# PM12_Supply_LED.net
KiCad netlist of a schematic drawn in Altium Designer
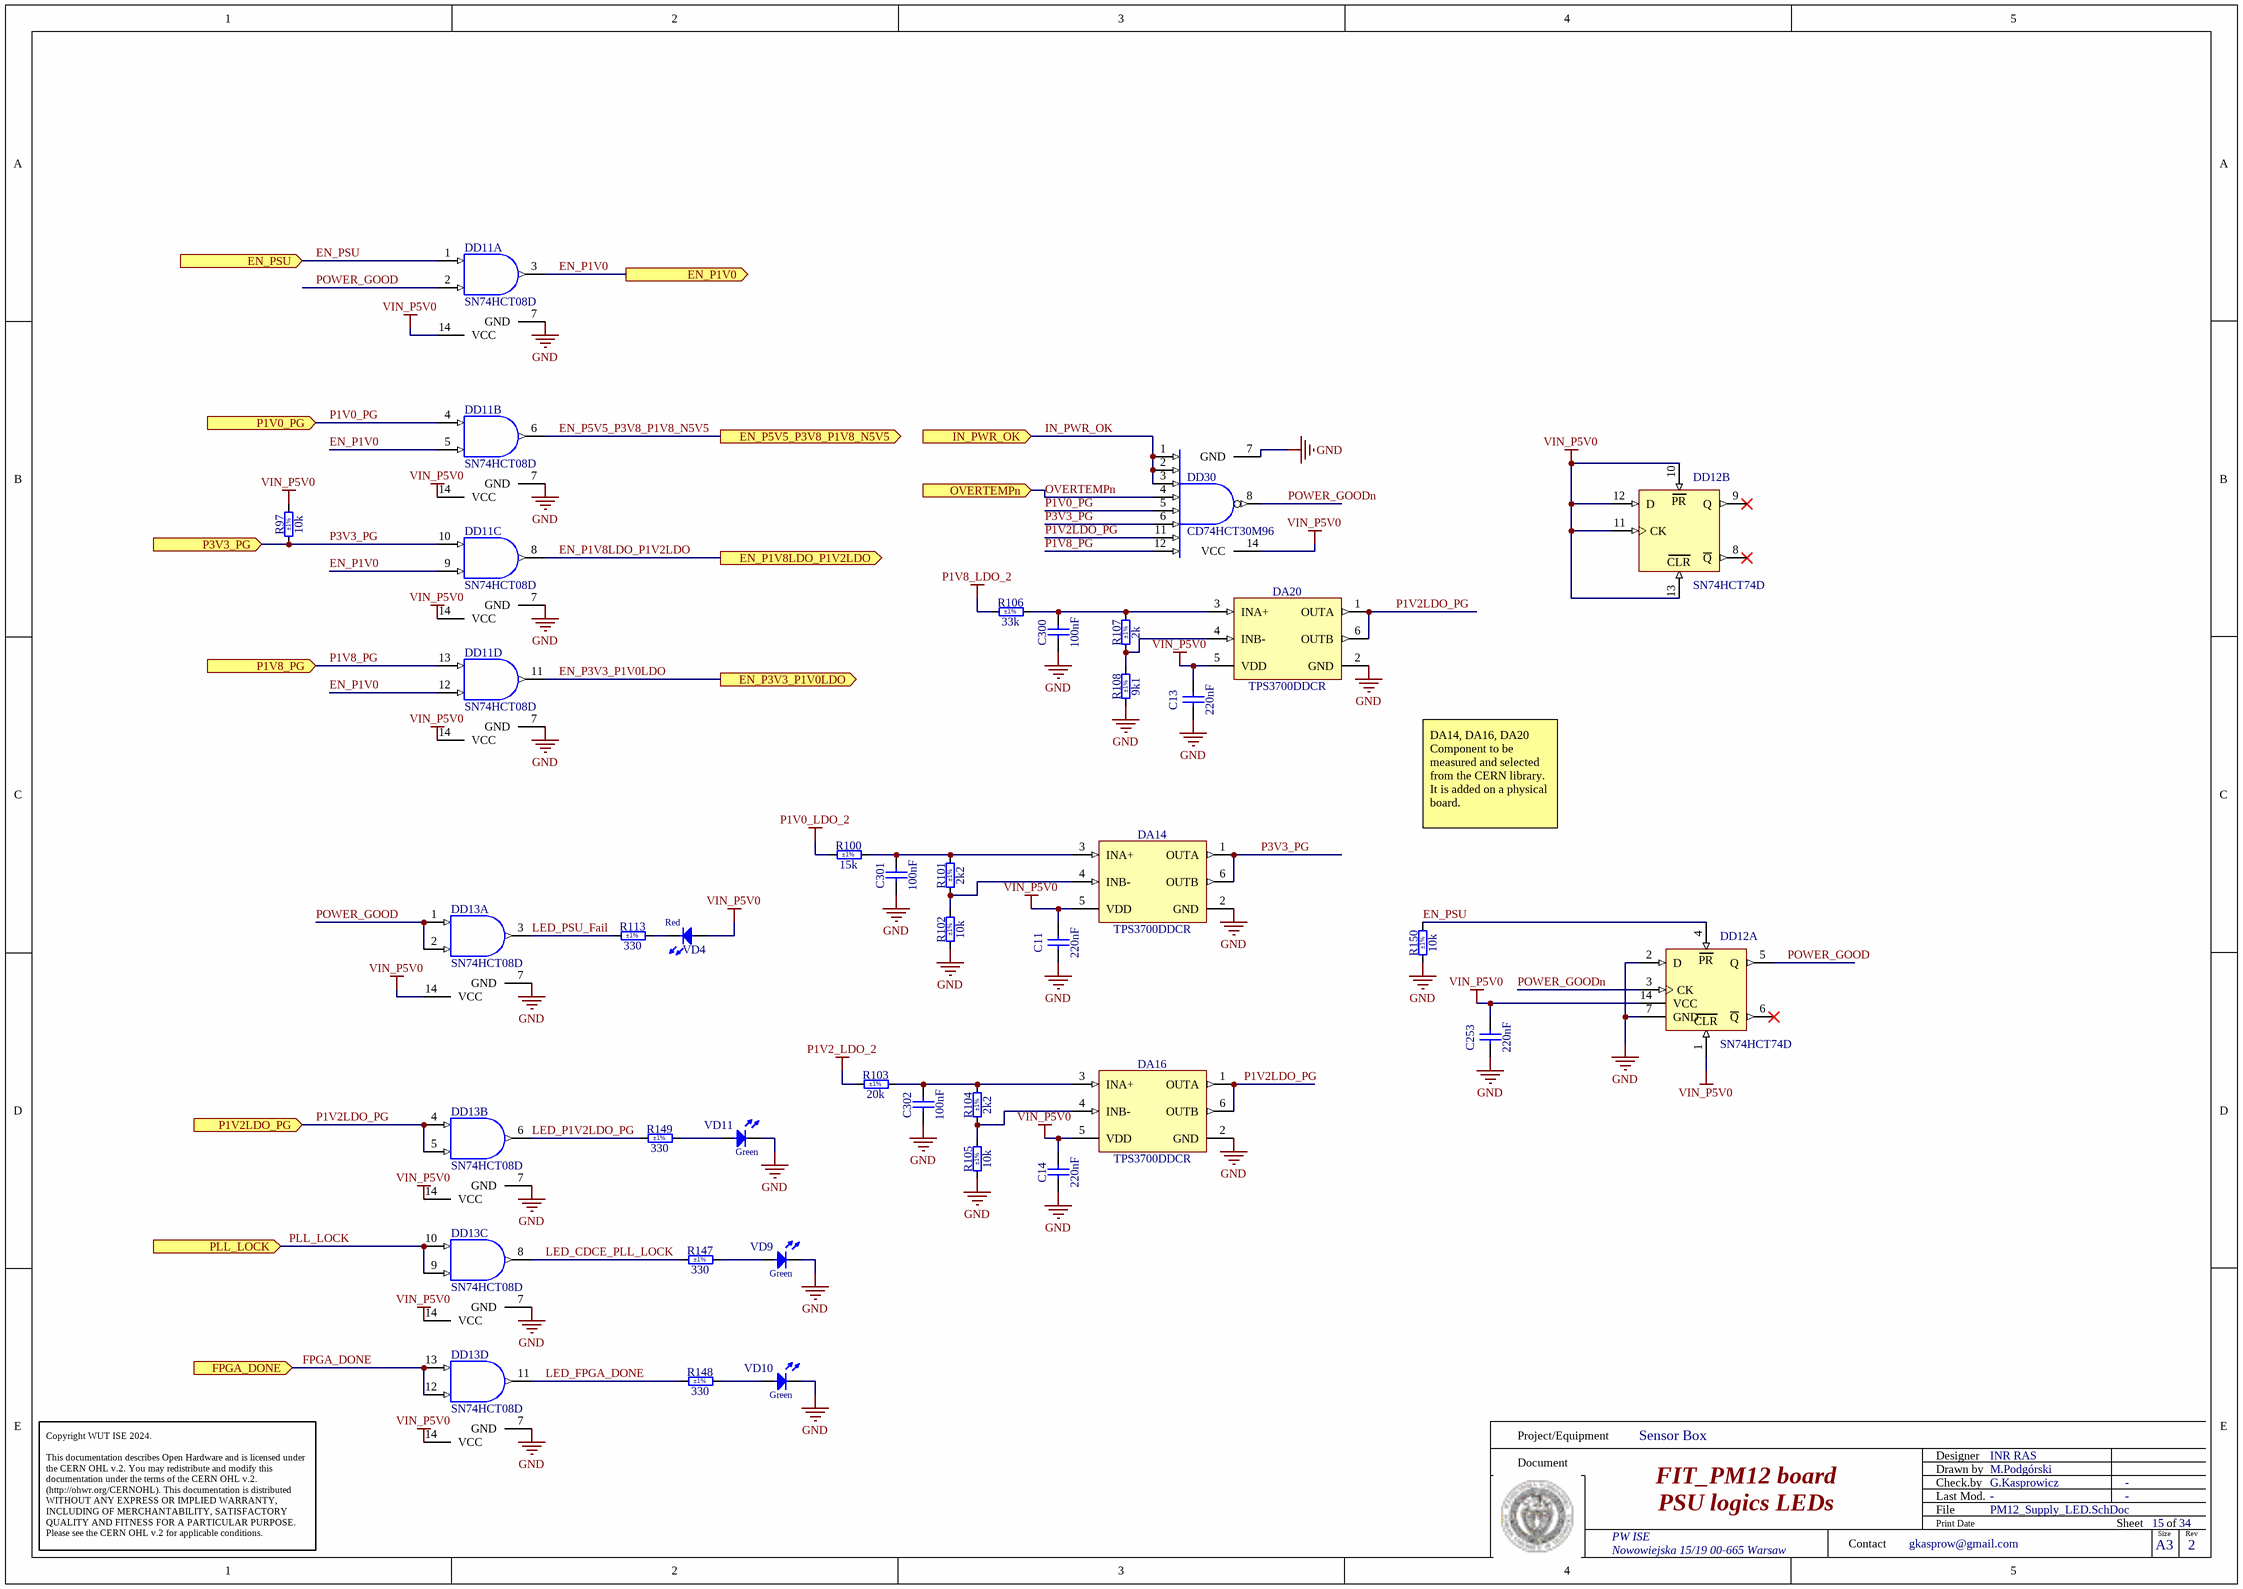
[diagram p0: PM12_Supply_LED.SchDoc]

(export (version "E")
  (design (tool "Eeschema 10.0.6"))
  (components
    (comp (ref "C11")
      (value "220nF")
      (footprint "CAPC2012X135N")
      (description "Non-polarised capacitor")
      (fields
        (field (name "PART NUMBER") "CC0805_220NF_50V_10%_X7R")
        (field (name "VOLTAGE") "50V")
        (field (name "AUTHOR") "CERN DEM JLC")
      )
      (libsource (lib "Capacitors") (part "Capacitor - non polarized"))
    )
    (comp (ref "C13")
      (value "220nF")
      (footprint "CAPC2012X135N")
      (description "Non-polarised capacitor")
      (fields
        (field (name "PART NUMBER") "CC0805_220NF_50V_10%_X7R")
        (field (name "VOLTAGE") "50V")
        (field (name "AUTHOR") "CERN DEM JLC")
      )
      (libsource (lib "Capacitors") (part "Capacitor - non polarized"))
    )
    (comp (ref "C14")
      (value "220nF")
      (footprint "CAPC2012X135N")
      (description "Non-polarised capacitor")
      (fields
        (field (name "PART NUMBER") "CC0805_220NF_50V_10%_X7R")
        (field (name "VOLTAGE") "50V")
        (field (name "AUTHOR") "CERN DEM JLC")
      )
      (libsource (lib "Capacitors") (part "Capacitor - non polarized"))
    )
    (comp (ref "C253")
      (value "220nF")
      (footprint "CAPC2012X135N")
      (description "Non-polarised capacitor")
      (fields
        (field (name "PART NUMBER") "CC0805_220NF_50V_10%_X7R")
        (field (name "VOLTAGE") "50V")
        (field (name "AUTHOR") "CERN DEM JLC")
      )
      (libsource (lib "Capacitors") (part "Capacitor - non polarized"))
    )
    (comp (ref "C300")
      (value "100nF")
      (footprint "CAPC1005X55N")
      (description "Non-polarised capacitor")
      (fields
        (field (name "PART NUMBER") "CC0402_100NF_50V_10%_X7R")
        (field (name "VOLTAGE") "50V")
        (field (name "AUTHOR") "CERN DEM MR")
      )
      (libsource (lib "Capacitors") (part "Capacitor - non polarized"))
    )
    (comp (ref "C301")
      (value "100nF")
      (footprint "CAPC1005X55N")
      (description "Non-polarised capacitor")
      (fields
        (field (name "PART NUMBER") "CC0402_100NF_50V_10%_X7R")
        (field (name "VOLTAGE") "50V")
        (field (name "AUTHOR") "CERN DEM MR")
      )
      (libsource (lib "Capacitors") (part "Capacitor - non polarized"))
    )
    (comp (ref "C302")
      (value "100nF")
      (footprint "CAPC1005X55N")
      (description "Non-polarised capacitor")
      (fields
        (field (name "PART NUMBER") "CC0402_100NF_50V_10%_X7R")
        (field (name "VOLTAGE") "50V")
        (field (name "AUTHOR") "CERN DEM MR")
      )
      (libsource (lib "Capacitors") (part "Capacitor - non polarized"))
    )
    (comp (ref "DA14")
      (value "TPS3700DDCR")
      (footprint "SOT95P280X110-6N")
      (description "Window Comparator for Over- and Undervoltage Detection")
      (fields (field (name "MANUFACTURER") "TEXAS INSTRUMENTS") (field (name "AUTHOR") "CERN DEM JMW"))
      (libsource (lib "ICs And Semiconductors") (part "TPS3700DDC"))
    )
    (comp (ref "DA16")
      (value "TPS3700DDCR")
      (footprint "SOT95P280X110-6N")
      (description "Window Comparator for Over- and Undervoltage Detection")
      (fields (field (name "MANUFACTURER") "TEXAS INSTRUMENTS") (field (name "AUTHOR") "CERN DEM JMW"))
      (libsource (lib "ICs And Semiconductors") (part "TPS3700DDC"))
    )
    (comp (ref "DA20")
      (value "TPS3700DDCR")
      (footprint "SOT95P280X110-6N")
      (description "Window Comparator for Over- and Undervoltage Detection")
      (fields (field (name "MANUFACTURER") "TEXAS INSTRUMENTS") (field (name "AUTHOR") "CERN DEM JMW"))
      (libsource (lib "ICs And Semiconductors") (part "TPS3700DDC"))
    )
    (comp (ref "DD11")
      (value "SN74HCT08D")
      (footprint "SOIC127P600X175-14N")
      (description "Quad 2-Input AND Gate")
      (fields (field (name "MANUFACTURER") "TEXAS INSTRUMENTS") (field (name "AUTHOR") "CERN DEM HF"))
      (libsource (lib "ICs And Semiconductors") (part "7408"))
    )
    (comp (ref "DD12")
      (value "SN74HCT74D")
      (footprint "SOIC127P600X175-14N")
      (description "Dual D-Type Flip Flop with Preset and Clear")
      (fields (field (name "MANUFACTURER") "TEXAS INSTRUMENTS") (field (name "AUTHOR") "CERN DEM JLC"))
      (libsource (lib "ICs And Semiconductors") (part "7474"))
    )
    (comp (ref "DD13")
      (value "SN74HCT08D")
      (footprint "SOIC127P600X175-14N")
      (description "Quad 2-Input AND Gate")
      (fields (field (name "MANUFACTURER") "TEXAS INSTRUMENTS") (field (name "AUTHOR") "CERN DEM HF"))
      (libsource (lib "ICs And Semiconductors") (part "7408"))
    )
    (comp (ref "DD30")
      (value "CD74HCT30M96")
      (footprint "SOIC127P600X175-14N")
      (description "8-Input NAND Gate")
      (fields (field (name "MANUFACTURER") "TEXAS INSTRUMENTS") (field (name "AUTHOR") "CERN DEM HF"))
      (libsource (lib "ICs And Semiconductors") (part "7430"))
    )
    (comp (ref "R97")
      (value "10k")
      (footprint "RESC2012X60N")
      (description "Resistor - 1%")
      (fields
        (field (name "TOLERANCE") "±1%")
        (field (name "PART NUMBER") "R0805_10K_1%_0.125W_100PPM")
        (field (name "POWER") "0.125W")
        (field (name "AUTHOR") "CERN DEM JLC")
      )
      (libsource (lib "Resistors") (part "Resistor - 1%"))
    )
    (comp (ref "R100")
      (value "15k")
      (footprint "RESC2012X60N")
      (description "Resistor - 1%")
      (fields
        (field (name "TOLERANCE") "±1%")
        (field (name "PART NUMBER") "R0805_15K_1%_0.125W_100PPM")
        (field (name "POWER") "0.125W")
        (field (name "AUTHOR") "CERN DEM JLC")
      )
      (libsource (lib "Resistors") (part "Resistor - 1%"))
    )
    (comp (ref "R101")
      (value "2k2")
      (footprint "RESC2012X60N")
      (description "Resistor - 1%")
      (fields
        (field (name "TOLERANCE") "±1%")
        (field (name "PART NUMBER") "R0805_2K2_1%_0.125W_100PPM")
        (field (name "POWER") "0.125W")
        (field (name "AUTHOR") "CERN DEM JLC")
      )
      (libsource (lib "Resistors") (part "Resistor - 1%"))
    )
    (comp (ref "R102")
      (value "10k")
      (footprint "RESC2012X60N")
      (description "Resistor - 1%")
      (fields
        (field (name "TOLERANCE") "±1%")
        (field (name "PART NUMBER") "R0805_10K_1%_0.125W_100PPM")
        (field (name "POWER") "0.125W")
        (field (name "AUTHOR") "CERN DEM JLC")
      )
      (libsource (lib "Resistors") (part "Resistor - 1%"))
    )
    (comp (ref "R103")
      (value "20k")
      (footprint "RESC2012X60N")
      (description "Resistor - 1%")
      (fields
        (field (name "TOLERANCE") "±1%")
        (field (name "PART NUMBER") "R0805_20K_1%_0.125W_100PPM")
        (field (name "POWER") "0.125W")
        (field (name "AUTHOR") "CERN DEM JLC")
      )
      (libsource (lib "Resistors") (part "Resistor - 1%"))
    )
    (comp (ref "R104")
      (value "2k2")
      (footprint "RESC2012X60N")
      (description "Resistor - 1%")
      (fields
        (field (name "TOLERANCE") "±1%")
        (field (name "PART NUMBER") "R0805_2K2_1%_0.125W_100PPM")
        (field (name "POWER") "0.125W")
        (field (name "AUTHOR") "CERN DEM JLC")
      )
      (libsource (lib "Resistors") (part "Resistor - 1%"))
    )
    (comp (ref "R105")
      (value "10k")
      (footprint "RESC2012X60N")
      (description "Resistor - 1%")
      (fields
        (field (name "TOLERANCE") "±1%")
        (field (name "PART NUMBER") "R0805_10K_1%_0.125W_100PPM")
        (field (name "POWER") "0.125W")
        (field (name "AUTHOR") "CERN DEM JLC")
      )
      (libsource (lib "Resistors") (part "Resistor - 1%"))
    )
    (comp (ref "R106")
      (value "33k")
      (footprint "RESC2012X60N")
      (description "Resistor - 1%")
      (fields
        (field (name "TOLERANCE") "±1%")
        (field (name "PART NUMBER") "R0805_33K_1%_0.125W_100PPM")
        (field (name "POWER") "0.125W")
        (field (name "AUTHOR") "CERN DEM JLC")
      )
      (libsource (lib "Resistors") (part "Resistor - 1%"))
    )
    (comp (ref "R107")
      (value "2k")
      (footprint "RESC2012X60N")
      (description "Resistor - 1%")
      (fields
        (field (name "TOLERANCE") "±1%")
        (field (name "PART NUMBER") "R0805_2K_1%_0.125W_100PPM")
        (field (name "POWER") "0.125W")
        (field (name "AUTHOR") "CERN DEM JLC")
      )
      (libsource (lib "Resistors") (part "Resistor - 1%"))
    )
    (comp (ref "R108")
      (value "9k1")
      (footprint "RESC2012X60N")
      (description "Resistor - 1%")
      (fields
        (field (name "TOLERANCE") "±1%")
        (field (name "PART NUMBER") "R0805_9K1_1%_0.125W_100PPM")
        (field (name "POWER") "0.125W")
        (field (name "AUTHOR") "CERN DEM JLC")
      )
      (libsource (lib "Resistors") (part "Resistor - 1%"))
    )
    (comp (ref "R113")
      (value "330")
      (footprint "RESC2012X60N")
      (description "Resistor - 1%")
      (fields
        (field (name "TOLERANCE") "±1%")
        (field (name "PART NUMBER") "R0805_330R_1%_0.125W_100PPM")
        (field (name "POWER") "0.125W")
        (field (name "AUTHOR") "CERN DEM JLC")
      )
      (libsource (lib "Resistors") (part "Resistor - 1%"))
    )
    (comp (ref "R147")
      (value "330")
      (footprint "RESC2012X60N")
      (description "Resistor - 1%")
      (fields
        (field (name "TOLERANCE") "±1%")
        (field (name "PART NUMBER") "R0805_330R_1%_0.125W_100PPM")
        (field (name "POWER") "0.125W")
        (field (name "AUTHOR") "CERN DEM JLC")
      )
      (libsource (lib "Resistors") (part "Resistor - 1%"))
    )
    (comp (ref "R148")
      (value "330")
      (footprint "RESC2012X60N")
      (description "Resistor - 1%")
      (fields
        (field (name "TOLERANCE") "±1%")
        (field (name "PART NUMBER") "R0805_330R_1%_0.125W_100PPM")
        (field (name "POWER") "0.125W")
        (field (name "AUTHOR") "CERN DEM JLC")
      )
      (libsource (lib "Resistors") (part "Resistor - 1%"))
    )
    (comp (ref "R149")
      (value "330")
      (footprint "RESC2012X60N")
      (description "Resistor - 1%")
      (fields
        (field (name "TOLERANCE") "±1%")
        (field (name "PART NUMBER") "R0805_330R_1%_0.125W_100PPM")
        (field (name "POWER") "0.125W")
        (field (name "AUTHOR") "CERN DEM JLC")
      )
      (libsource (lib "Resistors") (part "Resistor - 1%"))
    )
    (comp (ref "R150")
      (value "10k")
      (footprint "RESC2012X60N")
      (description "Resistor - 1%")
      (fields
        (field (name "TOLERANCE") "±1%")
        (field (name "PART NUMBER") "R0805_10K_1%_0.125W_100PPM")
        (field (name "POWER") "0.125W")
        (field (name "AUTHOR") "CERN DEM JLC")
      )
      (libsource (lib "Resistors") (part "Resistor - 1%"))
    )
    (comp (ref "VD4")
      (value "Red")
      (footprint "LED_KINGBRIGHT_KPT-2012SURCK")
      (description "LED Red 1C 2A")
      (fields
        (field (name "PART NUMBER") "LED_KINGBRIGHT_KPT-2012SURCK")
        (field (name "MANUFACTURER") "KINGBRIGHT")
        (field (name "AUTHOR") "CERN DEM BC")
      )
      (libsource (lib "ICs And Semiconductors") (part "LED Red 1C 2A"))
    )
    (comp (ref "VD9")
      (value "Green")
      (footprint "LED_KINGBRIGHT_KP-2012LSGC")
      (description "LED Green 1C 2A")
      (fields
        (field (name "PART NUMBER") "LED_KINGBRIGHT_KP-2012LSGC")
        (field (name "MANUFACTURER") "KINGBRIGHT")
        (field (name "AUTHOR") "CERN DEM BC")
      )
      (libsource (lib "ICs And Semiconductors") (part "LED Green 1C 2A"))
    )
    (comp (ref "VD10")
      (value "Green")
      (footprint "LED_KINGBRIGHT_KP-2012LSGC")
      (description "LED Green 1C 2A")
      (fields
        (field (name "PART NUMBER") "LED_KINGBRIGHT_KP-2012LSGC")
        (field (name "MANUFACTURER") "KINGBRIGHT")
        (field (name "AUTHOR") "CERN DEM BC")
      )
      (libsource (lib "ICs And Semiconductors") (part "LED Green 1C 2A"))
    )
    (comp (ref "VD11")
      (value "Green")
      (footprint "LED_KINGBRIGHT_KP-2012LSGC")
      (description "LED Green 1C 2A")
      (fields
        (field (name "PART NUMBER") "LED_KINGBRIGHT_KP-2012LSGC")
        (field (name "MANUFACTURER") "KINGBRIGHT")
        (field (name "AUTHOR") "CERN DEM BC")
      )
      (libsource (lib "ICs And Semiconductors") (part "LED Green 1C 2A"))
    )
  )
  (nets
    (net (code "1") (name "/EN_P1V0") (class "Default")
      (node (ref "DD11") (pin "12") (pinfunction "B_12") (pintype "input"))
      (node (ref "DD11") (pin "3") (pinfunction "Y_3") (pintype "output"))
      (node (ref "DD11") (pin "5") (pinfunction "B_5") (pintype "input"))
      (node (ref "DD11") (pin "9") (pinfunction "B_9") (pintype "input"))
    )
    (net (code "2") (name "/EN_P1V8LDO_P1V2LDO") (class "Default")
      (node (ref "DD11") (pin "8") (pinfunction "Y_8") (pintype "output"))
    )
    (net (code "3") (name "/EN_P3V3_P1V0LDO") (class "Default")
      (node (ref "DD11") (pin "11") (pinfunction "Y_11") (pintype "output"))
    )
    (net (code "4") (name "/EN_P5V5_P3V8_P1V8_N5V5") (class "Default")
      (node (ref "DD11") (pin "6") (pinfunction "Y_6") (pintype "output"))
    )
    (net (code "5") (name "/EN_PSU") (class "Default")
      (node (ref "DD11") (pin "1") (pinfunction "A_1") (pintype "input"))
      (node (ref "DD12") (pin "4") (pinfunction "~{PR}_4") (pintype "input"))
      (node (ref "R150") (pin "2") (pinfunction "2_2") (pintype "passive"))
    )
    (net (code "6") (name "/FPGA_DONE") (class "Default")
      (node (ref "DD13") (pin "12") (pinfunction "B_12") (pintype "input"))
      (node (ref "DD13") (pin "13") (pinfunction "A_13") (pintype "input"))
    )
    (net (code "7") (name "/IN_PWR_OK") (class "Default")
      (node (ref "DD30") (pin "1") (pinfunction "A_1") (pintype "input"))
      (node (ref "DD30") (pin "2") (pinfunction "B_2") (pintype "input"))
      (node (ref "DD30") (pin "3") (pinfunction "C_3") (pintype "input"))
    )
    (net (code "8") (name "/LED_CDCE_PLL_LOCK") (class "Default")
      (node (ref "DD13") (pin "8") (pinfunction "Y_8") (pintype "output"))
      (node (ref "R147") (pin "1") (pinfunction "1_1") (pintype "passive"))
    )
    (net (code "9") (name "/LED_FPGA_DONE") (class "Default")
      (node (ref "DD13") (pin "11") (pinfunction "Y_11") (pintype "output"))
      (node (ref "R148") (pin "1") (pinfunction "1_1") (pintype "passive"))
    )
    (net (code "10") (name "/LED_P1V2LDO_PG") (class "Default")
      (node (ref "DD13") (pin "6") (pinfunction "Y_6") (pintype "output"))
      (node (ref "R149") (pin "1") (pinfunction "1_1") (pintype "passive"))
    )
    (net (code "11") (name "/LED_PSU_Fail") (class "Default")
      (node (ref "DD13") (pin "3") (pinfunction "Y_3") (pintype "output"))
      (node (ref "R113") (pin "1") (pinfunction "1_1") (pintype "passive"))
    )
    (net (code "12") (name "/OVERTEMPn") (class "Default")
      (node (ref "DD30") (pin "4") (pinfunction "D_4") (pintype "input"))
    )
    (net (code "13") (name "/P1V0_PG") (class "Default")
      (node (ref "DD11") (pin "4") (pinfunction "A_4") (pintype "input"))
      (node (ref "DD30") (pin "5") (pinfunction "E_5") (pintype "input"))
    )
    (net (code "14") (name "/P1V2LDO_PG") (class "Default")
      (node (ref "DA16") (pin "1") (pinfunction "OUTA_1") (pintype "output"))
      (node (ref "DA16") (pin "6") (pinfunction "OUTB_6") (pintype "output"))
      (node (ref "DA20") (pin "1") (pinfunction "OUTA_1") (pintype "output"))
      (node (ref "DA20") (pin "6") (pinfunction "OUTB_6") (pintype "output"))
      (node (ref "DD13") (pin "4") (pinfunction "A_4") (pintype "input"))
      (node (ref "DD13") (pin "5") (pinfunction "B_5") (pintype "input"))
      (node (ref "DD30") (pin "11") (pinfunction "G_11") (pintype "input"))
    )
    (net (code "15") (name "/P1V8_PG") (class "Default")
      (node (ref "DD11") (pin "13") (pinfunction "A_13") (pintype "input"))
      (node (ref "DD30") (pin "12") (pinfunction "H_12") (pintype "input"))
    )
    (net (code "16") (name "/P3V3_PG") (class "Default")
      (node (ref "DA14") (pin "1") (pinfunction "OUTA_1") (pintype "output"))
      (node (ref "DA14") (pin "6") (pinfunction "OUTB_6") (pintype "output"))
      (node (ref "DD11") (pin "10") (pinfunction "A_10") (pintype "input"))
      (node (ref "DD30") (pin "6") (pinfunction "F_6") (pintype "input"))
      (node (ref "R97") (pin "1") (pinfunction "1_1") (pintype "passive"))
    )
    (net (code "17") (name "/PLL_LOCK") (class "Default")
      (node (ref "DD13") (pin "10") (pinfunction "A_10") (pintype "input"))
      (node (ref "DD13") (pin "9") (pinfunction "B_9") (pintype "input"))
    )
    (net (code "18") (name "/POWER_GOOD") (class "Default")
      (node (ref "DD11") (pin "2") (pinfunction "B_2") (pintype "input"))
      (node (ref "DD12") (pin "5") (pinfunction "Q_5") (pintype "output"))
      (node (ref "DD13") (pin "1") (pinfunction "A_1") (pintype "input"))
      (node (ref "DD13") (pin "2") (pinfunction "B_2") (pintype "input"))
    )
    (net (code "19") (name "/POWER_GOODn") (class "Default")
      (node (ref "DD12") (pin "3") (pinfunction "CK_3") (pintype "input"))
      (node (ref "DD30") (pin "8") (pinfunction "Y_8") (pintype "output"))
    )
    (net (code "20") (name "GND") (class "Default")
      (node (ref "C11") (pin "1") (pinfunction "1_1") (pintype "passive"))
      (node (ref "C13") (pin "1") (pinfunction "1_1") (pintype "passive"))
      (node (ref "C14") (pin "1") (pinfunction "1_1") (pintype "passive"))
      (node (ref "C253") (pin "1") (pinfunction "1_1") (pintype "passive"))
      (node (ref "C300") (pin "1") (pinfunction "1_1") (pintype "passive"))
      (node (ref "C301") (pin "1") (pinfunction "1_1") (pintype "passive"))
      (node (ref "C302") (pin "1") (pinfunction "1_1") (pintype "passive"))
      (node (ref "DA14") (pin "2") (pinfunction "GND_2") (pintype "power_in"))
      (node (ref "DA16") (pin "2") (pinfunction "GND_2") (pintype "power_in"))
      (node (ref "DA20") (pin "2") (pinfunction "GND_2") (pintype "power_in"))
      (node (ref "DD11") (pin "7") (pinfunction "GND_7") (pintype "power_in"))
      (node (ref "DD12") (pin "2") (pinfunction "D_2") (pintype "input"))
      (node (ref "DD12") (pin "7") (pinfunction "GND_7") (pintype "power_in"))
      (node (ref "DD13") (pin "7") (pinfunction "GND_7") (pintype "power_in"))
      (node (ref "DD30") (pin "7") (pinfunction "GND_7") (pintype "power_in"))
      (node (ref "R102") (pin "1") (pinfunction "1_1") (pintype "passive"))
      (node (ref "R105") (pin "1") (pinfunction "1_1") (pintype "passive"))
      (node (ref "R108") (pin "1") (pinfunction "1_1") (pintype "passive"))
      (node (ref "R150") (pin "1") (pinfunction "1_1") (pintype "passive"))
      (node (ref "VD10") (pin "1") (pinfunction "C_1") (pintype "passive"))
      (node (ref "VD11") (pin "1") (pinfunction "C_1") (pintype "passive"))
      (node (ref "VD9") (pin "1") (pinfunction "C_1") (pintype "passive"))
    )
    (net (code "21") (name "Net-(DA14-INA+)") (class "Default")
      (node (ref "C301") (pin "2") (pinfunction "2_2") (pintype "passive"))
      (node (ref "DA14") (pin "3") (pinfunction "INA+_3") (pintype "input"))
      (node (ref "R100") (pin "2") (pinfunction "2_2") (pintype "passive"))
      (node (ref "R101") (pin "2") (pinfunction "2_2") (pintype "passive"))
    )
    (net (code "22") (name "Net-(DA14-INB-)") (class "Default")
      (node (ref "DA14") (pin "4") (pinfunction "INB-_4") (pintype "input"))
      (node (ref "R101") (pin "1") (pinfunction "1_1") (pintype "passive"))
      (node (ref "R102") (pin "2") (pinfunction "2_2") (pintype "passive"))
    )
    (net (code "23") (name "Net-(DA16-INA+)") (class "Default")
      (node (ref "C302") (pin "2") (pinfunction "2_2") (pintype "passive"))
      (node (ref "DA16") (pin "3") (pinfunction "INA+_3") (pintype "input"))
      (node (ref "R103") (pin "2") (pinfunction "2_2") (pintype "passive"))
      (node (ref "R104") (pin "2") (pinfunction "2_2") (pintype "passive"))
    )
    (net (code "24") (name "Net-(DA16-INB-)") (class "Default")
      (node (ref "DA16") (pin "4") (pinfunction "INB-_4") (pintype "input"))
      (node (ref "R104") (pin "1") (pinfunction "1_1") (pintype "passive"))
      (node (ref "R105") (pin "2") (pinfunction "2_2") (pintype "passive"))
    )
    (net (code "25") (name "Net-(DA20-INA+)") (class "Default")
      (node (ref "C300") (pin "2") (pinfunction "2_2") (pintype "passive"))
      (node (ref "DA20") (pin "3") (pinfunction "INA+_3") (pintype "input"))
      (node (ref "R106") (pin "2") (pinfunction "2_2") (pintype "passive"))
      (node (ref "R107") (pin "2") (pinfunction "2_2") (pintype "passive"))
    )
    (net (code "26") (name "Net-(DA20-INB-)") (class "Default")
      (node (ref "DA20") (pin "4") (pinfunction "INB-_4") (pintype "input"))
      (node (ref "R107") (pin "1") (pinfunction "1_1") (pintype "passive"))
      (node (ref "R108") (pin "2") (pinfunction "2_2") (pintype "passive"))
    )
    (net (code "27") (name "Net-(VD4-C)") (class "Default")
      (node (ref "R113") (pin "2") (pinfunction "2_2") (pintype "passive"))
      (node (ref "VD4") (pin "1") (pinfunction "C_1") (pintype "passive"))
    )
    (net (code "28") (name "Net-(VD9-A)") (class "Default")
      (node (ref "R147") (pin "2") (pinfunction "2_2") (pintype "passive"))
      (node (ref "VD9") (pin "2") (pinfunction "A_2") (pintype "passive"))
    )
    (net (code "29") (name "Net-(VD10-A)") (class "Default")
      (node (ref "R148") (pin "2") (pinfunction "2_2") (pintype "passive"))
      (node (ref "VD10") (pin "2") (pinfunction "A_2") (pintype "passive"))
    )
    (net (code "30") (name "Net-(VD11-A)") (class "Default")
      (node (ref "R149") (pin "2") (pinfunction "2_2") (pintype "passive"))
      (node (ref "VD11") (pin "2") (pinfunction "A_2") (pintype "passive"))
    )
    (net (code "31") (name "P1V0_LDO_2") (class "Default")
      (node (ref "R100") (pin "1") (pinfunction "1_1") (pintype "passive"))
    )
    (net (code "32") (name "P1V2_LDO_2") (class "Default")
      (node (ref "R103") (pin "1") (pinfunction "1_1") (pintype "passive"))
    )
    (net (code "33") (name "P1V8_LDO_2") (class "Default")
      (node (ref "R106") (pin "1") (pinfunction "1_1") (pintype "passive"))
    )
    (net (code "34") (name "VIN_P5V0") (class "Default")
      (node (ref "C11") (pin "2") (pinfunction "2_2") (pintype "passive"))
      (node (ref "C13") (pin "2") (pinfunction "2_2") (pintype "passive"))
      (node (ref "C14") (pin "2") (pinfunction "2_2") (pintype "passive"))
      (node (ref "C253") (pin "2") (pinfunction "2_2") (pintype "passive"))
      (node (ref "DA14") (pin "5") (pinfunction "VDD_5") (pintype "power_in"))
      (node (ref "DA16") (pin "5") (pinfunction "VDD_5") (pintype "power_in"))
      (node (ref "DA20") (pin "5") (pinfunction "VDD_5") (pintype "power_in"))
      (node (ref "DD11") (pin "14") (pinfunction "VCC_14") (pintype "power_in"))
      (node (ref "DD12") (pin "1") (pinfunction "~{CLR}_1") (pintype "input"))
      (node (ref "DD12") (pin "10") (pinfunction "~{PR}_10") (pintype "input"))
      (node (ref "DD12") (pin "11") (pinfunction "CK_11") (pintype "input"))
      (node (ref "DD12") (pin "12") (pinfunction "D_12") (pintype "input"))
      (node (ref "DD12") (pin "13") (pinfunction "~{CLR}_13") (pintype "input"))
      (node (ref "DD12") (pin "14") (pinfunction "VCC_14") (pintype "power_in"))
      (node (ref "DD13") (pin "14") (pinfunction "VCC_14") (pintype "power_in"))
      (node (ref "DD30") (pin "14") (pinfunction "VCC_14") (pintype "power_in"))
      (node (ref "R97") (pin "2") (pinfunction "2_2") (pintype "passive"))
      (node (ref "VD4") (pin "2") (pinfunction "A_2") (pintype "passive"))
    )
    (net (code "35") (name "unconnected-(DD12A-~{Q}-Pad6)") (class "Default")
      (node (ref "DD12") (pin "6") (pinfunction "~{Q}_6") (pintype "output+no_connect"))
    )
    (net (code "36") (name "unconnected-(DD12B-Q-Pad9)") (class "Default")
      (node (ref "DD12") (pin "9") (pinfunction "Q_9") (pintype "output+no_connect"))
    )
    (net (code "37") (name "unconnected-(DD12B-~{Q}-Pad8)") (class "Default")
      (node (ref "DD12") (pin "8") (pinfunction "~{Q}_8") (pintype "output+no_connect"))
    )
  )
)
